# design.net
KiCad netlist of a schematic drawn in Altium Designer
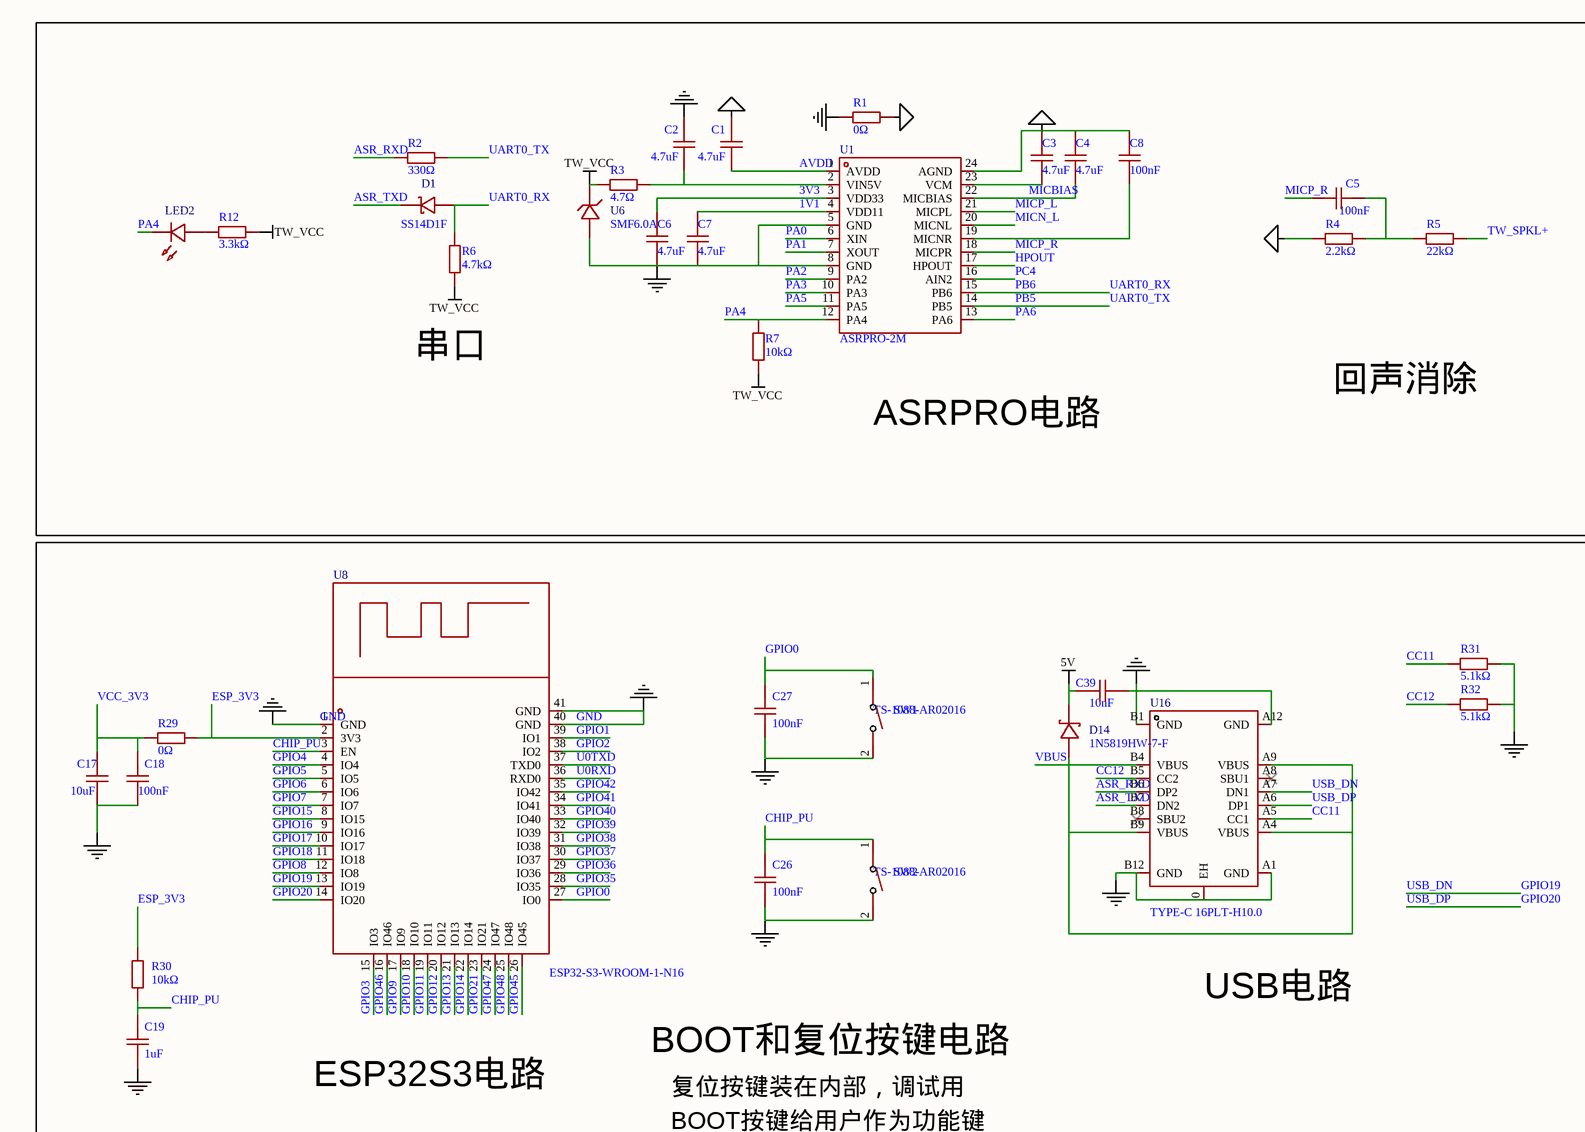
[diagram p0: 遥控器板子.schdoc, top left]
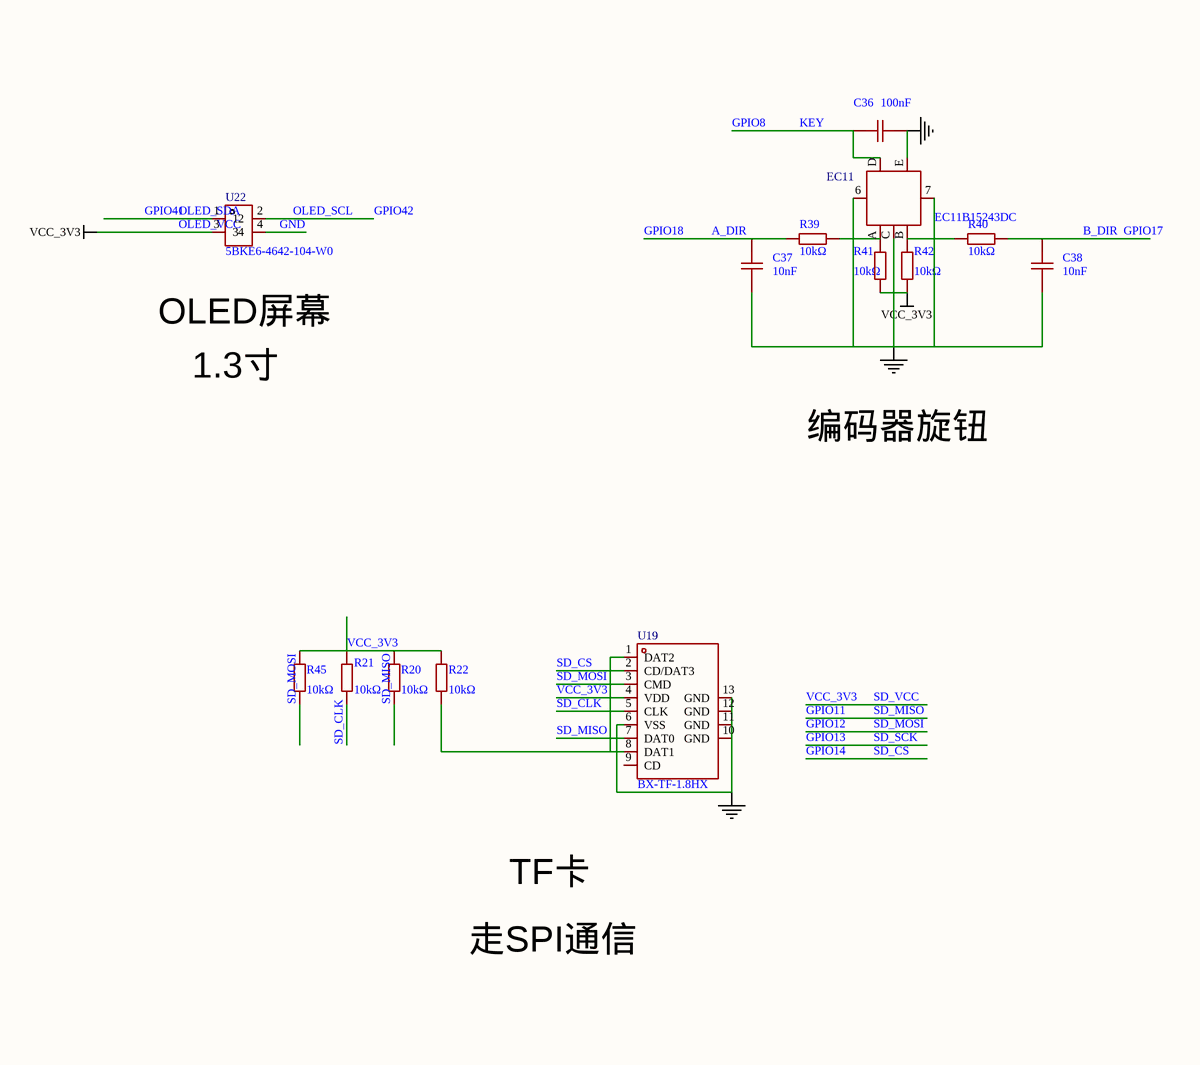
[diagram p1: 遥控器板子.schdoc, top right]
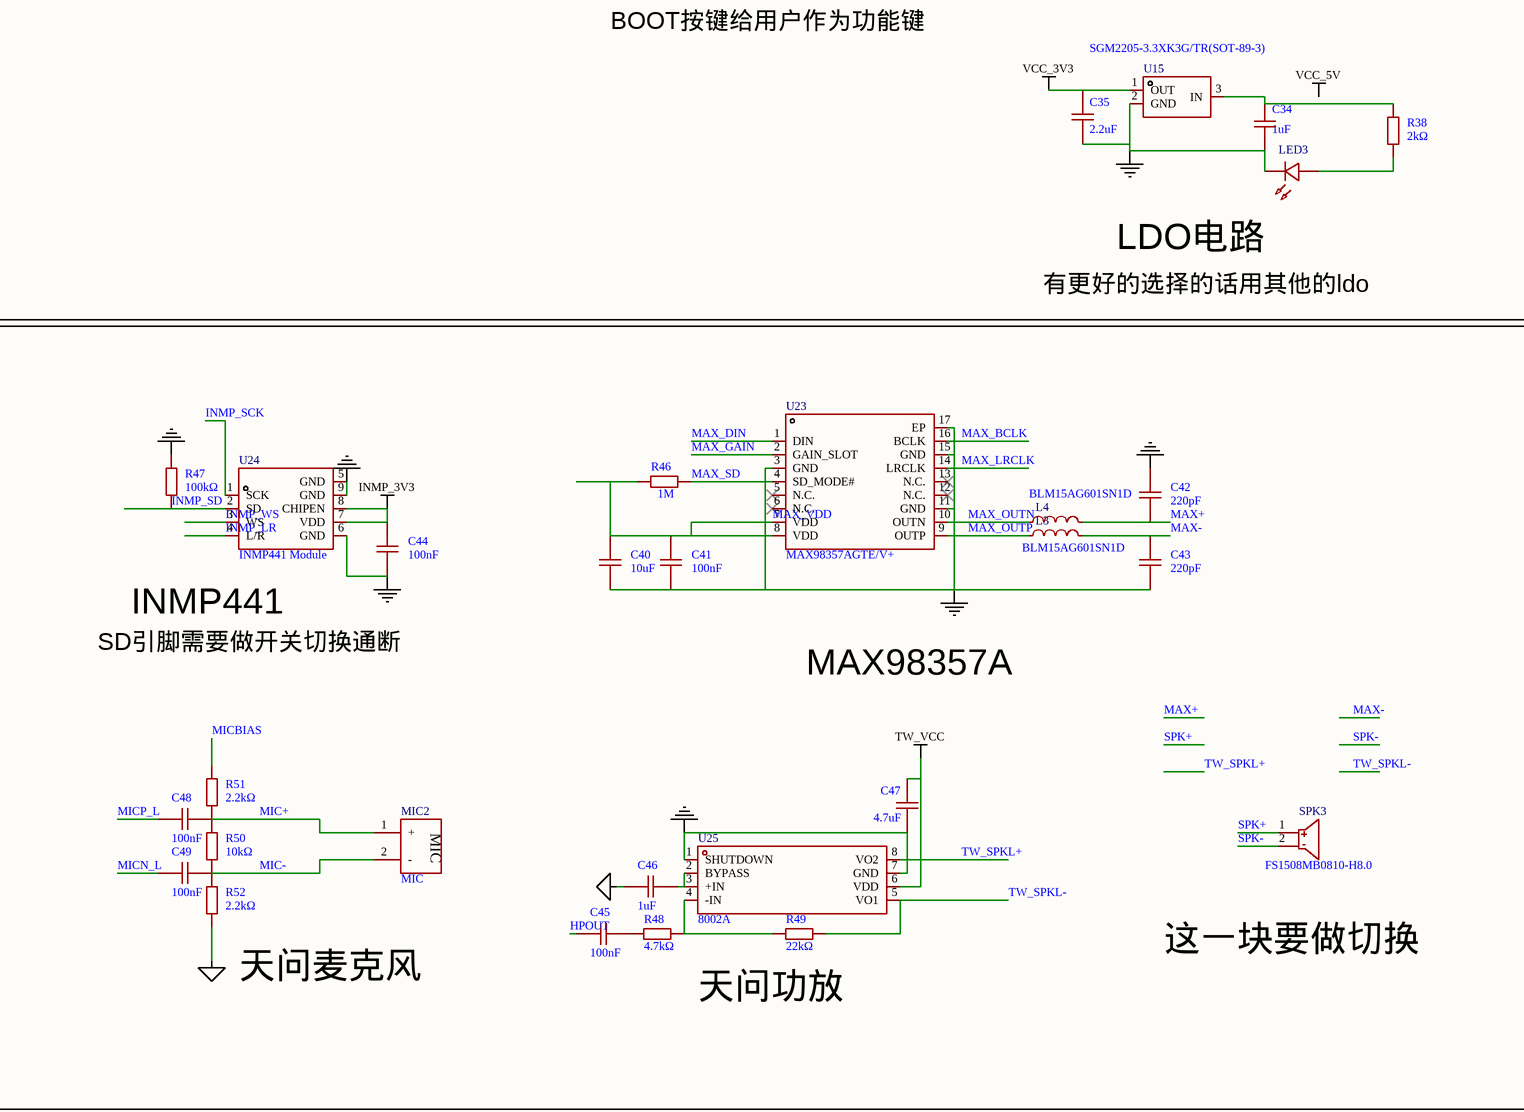
[diagram p2: 遥控器板子.schdoc, bottom left]
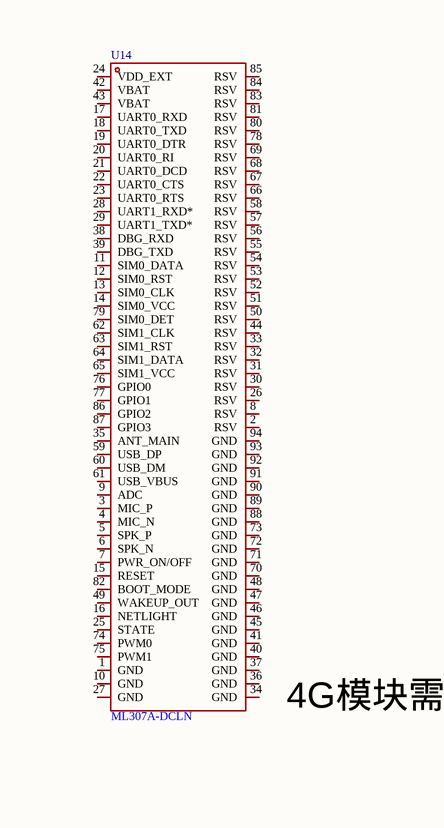
[diagram p3: 遥控器板子.schdoc, bottom right]

(export (version "E")
  (design (tool "Eeschema 10.0.6"))
  (components
    (comp (ref "C1")
      (value "4.7uF")
      (footprint "C0402")
      (fields
        (field (name "MANUFACTURER") "SAMSUNG(三星)")
        (field (name "MANUFACTURER PART") "CL05A475MP5NRNC")
        (field (name "TOLERANCE") "±20%")
      )
      (libsource (lib "altium-import") (part "root_1_CL05A475MP5NRNC_"))
    )
    (comp (ref "C2")
      (value "4.7uF")
      (footprint "C0402")
      (fields
        (field (name "MANUFACTURER") "SAMSUNG(三星)")
        (field (name "MANUFACTURER PART") "CL05A475MP5NRNC")
        (field (name "TOLERANCE") "±20%")
      )
      (libsource (lib "altium-import") (part "root_1_CL05A475MP5NRNC_"))
    )
    (comp (ref "C3")
      (value "4.7uF")
      (footprint "C0402")
      (fields
        (field (name "MANUFACTURER") "SAMSUNG(三星)")
        (field (name "MANUFACTURER PART") "CL05A475MP5NRNC")
        (field (name "TOLERANCE") "±20%")
      )
      (libsource (lib "altium-import") (part "root_1_CL05A475MP5NRNC_"))
    )
    (comp (ref "C4")
      (value "4.7uF")
      (footprint "C0402")
      (fields
        (field (name "MANUFACTURER") "SAMSUNG(三星)")
        (field (name "MANUFACTURER PART") "CL05A475MP5NRNC")
        (field (name "TOLERANCE") "±20%")
      )
      (libsource (lib "altium-import") (part "root_1_CL05A475MP5NRNC_"))
    )
    (comp (ref "C5")
      (value "100nF")
      (footprint "C0402")
      (fields
        (field (name "MANUFACTURER") "SAMSUNG(三星)")
        (field (name "MANUFACTURER PART") "CL05B104KO5NNNC")
        (field (name "TOLERANCE") "±10%")
      )
      (libsource (lib "altium-import") (part "root_0_CL05B104KO5NNNC_"))
    )
    (comp (ref "C6")
      (value "4.7uF")
      (footprint "C0402")
      (fields
        (field (name "MANUFACTURER") "SAMSUNG(三星)")
        (field (name "MANUFACTURER PART") "CL05A475MP5NRNC")
        (field (name "TOLERANCE") "±20%")
      )
      (libsource (lib "altium-import") (part "root_1_CL05A475MP5NRNC_"))
    )
    (comp (ref "C7")
      (value "4.7uF")
      (footprint "C0402")
      (fields
        (field (name "MANUFACTURER") "SAMSUNG(三星)")
        (field (name "MANUFACTURER PART") "CL05A475MP5NRNC")
        (field (name "TOLERANCE") "±20%")
      )
      (libsource (lib "altium-import") (part "root_1_CL05A475MP5NRNC_"))
    )
    (comp (ref "C8")
      (value "100nF")
      (footprint "C0402")
      (fields
        (field (name "MANUFACTURER") "SAMSUNG(三星)")
        (field (name "MANUFACTURER PART") "CL05B104KO5NNNC")
        (field (name "TOLERANCE") "±10%")
      )
      (libsource (lib "altium-import") (part "root_1_CL05B104KO5NNNC_"))
    )
    (comp (ref "C17")
      (value "10uF")
      (footprint "C0402")
      (fields
        (field (name "MANUFACTURER") "SAMSUNG(三星)")
        (field (name "MANUFACTURER PART") "CL05A106MQ5NUNC")
        (field (name "TOLERANCE") "±20%")
      )
      (libsource (lib "altium-import") (part "root_1_CL05A106MQ5NUNC_"))
    )
    (comp (ref "C18")
      (value "100nF")
      (footprint "C0402")
      (fields
        (field (name "MANUFACTURER") "SAMSUNG(三星)")
        (field (name "MANUFACTURER PART") "CL05B104KO5NNNC")
        (field (name "TOLERANCE") "±10%")
      )
      (libsource (lib "altium-import") (part "root_1_CL05B104KO5NNNC_"))
    )
    (comp (ref "C19")
      (value "1uF")
      (footprint "C0402")
      (fields
        (field (name "MANUFACTURER") "SAMSUNG(三星)")
        (field (name "MANUFACTURER PART") "CL05A105KP5NNNC")
        (field (name "TOLERANCE") "±10%")
      )
      (libsource (lib "altium-import") (part "root_1_CL05A105KP5NNNC_"))
    )
    (comp (ref "C26")
      (value "100nF")
      (footprint "C0402")
      (fields
        (field (name "MANUFACTURER") "SAMSUNG(三星)")
        (field (name "MANUFACTURER PART") "CL05B104KO5NNNC")
        (field (name "TOLERANCE") "±10%")
      )
      (libsource (lib "altium-import") (part "root_1_CL05B104KO5NNNC_"))
    )
    (comp (ref "C27")
      (value "100nF")
      (footprint "C0402")
      (fields
        (field (name "MANUFACTURER") "SAMSUNG(三星)")
        (field (name "MANUFACTURER PART") "CL05B104KO5NNNC")
        (field (name "TOLERANCE") "±10%")
      )
      (libsource (lib "altium-import") (part "root_1_CL05B104KO5NNNC_"))
    )
    (comp (ref "C34")
      (value "1uF")
      (footprint "C0402")
      (fields
        (field (name "MANUFACTURER") "SAMSUNG(三星)")
        (field (name "MANUFACTURER PART") "CL05A105KP5NNNC")
        (field (name "TOLERANCE") "±10%")
      )
      (libsource (lib "altium-import") (part "root_1_CL05A105KP5NNNC_"))
    )
    (comp (ref "C35")
      (value "2.2uF")
      (footprint "C0402")
      (fields
        (field (name "MANUFACTURER") "SAMSUNG(三星)")
        (field (name "MANUFACTURER PART") "CL05A225MQ5NSNC")
        (field (name "TOLERANCE") "±20%")
      )
      (libsource (lib "altium-import") (part "root_3_CL05A225MQ5NSNC_"))
    )
    (comp (ref "C36")
      (value "100nF")
      (footprint "C0402")
      (fields
        (field (name "MANUFACTURER") "SAMSUNG(三星)")
        (field (name "MANUFACTURER PART") "CL05B104KO5NNNC")
        (field (name "TOLERANCE") "±10%")
      )
      (libsource (lib "altium-import") (part "root_2_CL05B104KO5NNNC_"))
    )
    (comp (ref "C37")
      (value "10nF")
      (footprint "C0402")
      (fields
        (field (name "MANUFACTURER") "SAMSUNG(三星)")
        (field (name "MANUFACTURER PART") "CL05B103KB5NNNC")
        (field (name "TOLERANCE") "±10%")
      )
      (libsource (lib "altium-import") (part "root_1_CL05B103KB5NNNC_"))
    )
    (comp (ref "C38")
      (value "10nF")
      (footprint "C0402")
      (fields
        (field (name "MANUFACTURER") "SAMSUNG(三星)")
        (field (name "MANUFACTURER PART") "CL05B103KB5NNNC")
        (field (name "TOLERANCE") "±10%")
      )
      (libsource (lib "altium-import") (part "root_1_CL05B103KB5NNNC_"))
    )
    (comp (ref "C39")
      (value "10nF")
      (footprint "C0402")
      (fields
        (field (name "MANUFACTURER") "SAMSUNG(三星)")
        (field (name "MANUFACTURER PART") "CL05B103KB5NNNC")
        (field (name "TOLERANCE") "±10%")
      )
      (libsource (lib "altium-import") (part "root_0_CL05B103KB5NNNC_"))
    )
    (comp (ref "C40")
      (value "10uF")
      (footprint "C0402")
      (fields
        (field (name "MANUFACTURER") "SAMSUNG(三星)")
        (field (name "MANUFACTURER PART") "CL05A106MQ5NUNC")
        (field (name "TOLERANCE") "±20%")
      )
      (libsource (lib "altium-import") (part "root_1_CL05A106MQ5NUNC_"))
    )
    (comp (ref "C41")
      (value "100nF")
      (footprint "C0402")
      (fields
        (field (name "MANUFACTURER") "SAMSUNG(三星)")
        (field (name "MANUFACTURER PART") "CL05B104KO5NNNC")
        (field (name "TOLERANCE") "±10%")
      )
      (libsource (lib "altium-import") (part "root_1_CL05B104KO5NNNC_"))
    )
    (comp (ref "C42")
      (value "220pF")
      (footprint "C0402")
      (libsource (lib "altium-import") (part "root_1_CAP_0402_"))
    )
    (comp (ref "C43")
      (value "220pF")
      (footprint "C0402")
      (libsource (lib "altium-import") (part "root_1_CAP_0402_"))
    )
    (comp (ref "C44")
      (value "100nF")
      (footprint "C0402")
      (fields
        (field (name "MANUFACTURER") "SAMSUNG(三星)")
        (field (name "MANUFACTURER PART") "CL05B104KO5NNNC")
        (field (name "TOLERANCE") "±10%")
      )
      (libsource (lib "altium-import") (part "root_1_CL05B104KO5NNNC_"))
    )
    (comp (ref "C45")
      (value "100nF")
      (footprint "C0402")
      (fields
        (field (name "MANUFACTURER") "SAMSUNG(三星)")
        (field (name "MANUFACTURER PART") "CL05B104KO5NNNC")
        (field (name "TOLERANCE") "±10%")
      )
      (libsource (lib "altium-import") (part "root_2_CL05B104KO5NNNC_"))
    )
    (comp (ref "C46")
      (value "1uF")
      (footprint "C0402")
      (fields
        (field (name "MANUFACTURER") "SAMSUNG(三星)")
        (field (name "MANUFACTURER PART") "CL05A105KP5NNNC")
        (field (name "TOLERANCE") "±10%")
      )
      (libsource (lib "altium-import") (part "root_2_CL05A105KP5NNNC_"))
    )
    (comp (ref "C47")
      (value "4.7uF")
      (footprint "C0402")
      (fields
        (field (name "MANUFACTURER") "SAMSUNG(三星)")
        (field (name "MANUFACTURER PART") "CL05A475MP5NRNC")
        (field (name "TOLERANCE") "±20%")
      )
      (libsource (lib "altium-import") (part "root_3_CL05A475MP5NRNC_"))
    )
    (comp (ref "C48")
      (value "100nF")
      (footprint "C0402")
      (fields
        (field (name "MANUFACTURER") "SAMSUNG(三星)")
        (field (name "MANUFACTURER PART") "CL05B104KO5NNNC")
        (field (name "TOLERANCE") "±10%")
      )
      (libsource (lib "altium-import") (part "root_2_CL05B104KO5NNNC_"))
    )
    (comp (ref "C49")
      (value "100nF")
      (footprint "C0402")
      (fields
        (field (name "MANUFACTURER") "SAMSUNG(三星)")
        (field (name "MANUFACTURER PART") "CL05B104KO5NNNC")
        (field (name "TOLERANCE") "±10%")
      )
      (libsource (lib "altium-import") (part "root_2_CL05B104KO5NNNC_"))
    )
    (comp (ref "D1")
      (value "SS14D1F")
      (footprint "SOD-123_L2.8-W1.8-LS3.7-RD")
      (fields (field (name "MANUFACTURER") "PN SILICON(智晶)"))
      (libsource (lib "altium-import") (part "root_0_SS14D1F_"))
    )
    (comp (ref "D14")
      (value "1N5819HW-7-F")
      (footprint "SOD-123_L2.7-W1.6-LS3.7-RD")
      (fields (field (name "MANUFACTURER") "DIODES(美台)"))
      (libsource (lib "altium-import") (part "root_3_1N5819HW-7-F_"))
    )
    (comp (ref "EC11")
      (value "EC11B15243DC")
      (footprint "SW-TH_EC11B15243DC")
      (fields (field (name "MANUFACTURER") "ALPSALPINE(阿尔卑斯阿尔派)"))
      (libsource (lib "altium-import") (part "root_0_EC11B15243DC_"))
    )
    (comp (ref "L3")
      (value "BLM15AG601SN1D")
      (footprint "L0402")
      (fields (field (name "MANUFACTURER") "muRata(村田)") (field (name "TOLERANCE") "±25%"))
      (libsource (lib "altium-import") (part "root_0_BLM15AG601SN1D_"))
    )
    (comp (ref "L4")
      (value "BLM15AG601SN1D")
      (footprint "L0402")
      (fields (field (name "MANUFACTURER") "muRata(村田)") (field (name "TOLERANCE") "±25%"))
      (libsource (lib "altium-import") (part "root_0_BLM15AG601SN1D_"))
    )
    (comp (ref "LED2")
      (value "~")
      (footprint "LED_0402")
      (libsource (lib "altium-import") (part "root_2_LED_0603-R_"))
    )
    (comp (ref "LED3")
      (value "~")
      (footprint "LED_0402")
      (libsource (lib "altium-import") (part "root_2_LED_0603-R_"))
    )
    (comp (ref "MIC2")
      (value "MIC")
      (footprint "MIC-TH_BD6.0-P2.00")
      (libsource (lib "altium-import") (part "root_3_MIC_"))
    )
    (comp (ref "R1")
      (value "0Ω")
      (footprint "R0402")
      (fields
        (field (name "MANUFACTURER") "UNI-ROYAL(厚声)")
        (field (name "MANUFACTURER PART") "0402WGF0000TCE")
        (field (name "TOLERANCE") "±1%")
      )
      (libsource (lib "altium-import") (part "root_0_0402WGF0000TCE_"))
    )
    (comp (ref "R2")
      (value "330Ω")
      (footprint "R0402")
      (fields
        (field (name "MANUFACTURER") "UNI-ROYAL(厚声)")
        (field (name "MANUFACTURER PART") "0402WGF3300TCE")
        (field (name "TOLERANCE") "±1%")
      )
      (libsource (lib "altium-import") (part "root_0_0402WGF3300TCE_"))
    )
    (comp (ref "R3")
      (value "4.7Ω")
      (footprint "R0402")
      (fields
        (field (name "MANUFACTURER") "FOJAN(富捷)")
        (field (name "MANUFACTURER PART") "FRC0402F4R70TS")
        (field (name "TOLERANCE") "±1%")
      )
      (libsource (lib "altium-import") (part "root_0_FRC0402F4R70TS_"))
    )
    (comp (ref "R4")
      (value "2.2kΩ")
      (footprint "R0402")
      (fields
        (field (name "MANUFACTURER") "UNI-ROYAL(厚声)")
        (field (name "MANUFACTURER PART") "0402WGF2201TCE")
        (field (name "TOLERANCE") "±1%")
      )
      (libsource (lib "altium-import") (part "root_0_0402WGF2201TCE_"))
    )
    (comp (ref "R5")
      (value "22kΩ")
      (footprint "R0402")
      (fields
        (field (name "MANUFACTURER") "UNI-ROYAL(厚声)")
        (field (name "MANUFACTURER PART") "0402WGF2202TCE")
        (field (name "TOLERANCE") "±1%")
      )
      (libsource (lib "altium-import") (part "root_0_0402WGF2202TCE_"))
    )
    (comp (ref "R6")
      (value "4.7kΩ")
      (footprint "R0402")
      (fields
        (field (name "MANUFACTURER") "UNI-ROYAL(厚声)")
        (field (name "MANUFACTURER PART") "0402WGF4701TCE")
        (field (name "TOLERANCE") "±1%")
      )
      (libsource (lib "altium-import") (part "root_1_0402WGF4701TCE_"))
    )
    (comp (ref "R7")
      (value "10kΩ")
      (footprint "R0402")
      (fields
        (field (name "MANUFACTURER") "UNI-ROYAL(厚声)")
        (field (name "MANUFACTURER PART") "0402WGF1002TCE")
        (field (name "TOLERANCE") "±1%")
      )
      (libsource (lib "altium-import") (part "root_1_0402WGF1002TCE_"))
    )
    (comp (ref "R12")
      (value "3.3kΩ")
      (footprint "R0402")
      (fields
        (field (name "MANUFACTURER") "UNI-ROYAL(厚声)")
        (field (name "MANUFACTURER PART") "0402WGF3301TCE")
        (field (name "TOLERANCE") "±1%")
      )
      (libsource (lib "altium-import") (part "root_2_0402WGF3301TCE_"))
    )
    (comp (ref "R20")
      (value "10kΩ")
      (footprint "R0402")
      (fields
        (field (name "MANUFACTURER") "UNI-ROYAL(厚声)")
        (field (name "MANUFACTURER PART") "0402WGF1002TCE")
        (field (name "TOLERANCE") "±1%")
      )
      (libsource (lib "altium-import") (part "root_3_0402WGF1002TCE_"))
    )
    (comp (ref "R21")
      (value "10kΩ")
      (footprint "R0402")
      (fields
        (field (name "MANUFACTURER") "UNI-ROYAL(厚声)")
        (field (name "MANUFACTURER PART") "0402WGF1002TCE")
        (field (name "TOLERANCE") "±1%")
      )
      (libsource (lib "altium-import") (part "root_3_0402WGF1002TCE_"))
    )
    (comp (ref "R22")
      (value "10kΩ")
      (footprint "R0402")
      (fields
        (field (name "MANUFACTURER") "UNI-ROYAL(厚声)")
        (field (name "MANUFACTURER PART") "0402WGF1002TCE")
        (field (name "TOLERANCE") "±1%")
      )
      (libsource (lib "altium-import") (part "root_3_0402WGF1002TCE_"))
    )
    (comp (ref "R29")
      (value "0Ω")
      (footprint "R0402")
      (fields
        (field (name "MANUFACTURER") "UNI-ROYAL(厚声)")
        (field (name "MANUFACTURER PART") "0402WGF0000TCE")
        (field (name "TOLERANCE") "±1%")
      )
      (libsource (lib "altium-import") (part "root_0_0402WGF0000TCE_"))
    )
    (comp (ref "R30")
      (value "10kΩ")
      (footprint "R0402")
      (fields
        (field (name "MANUFACTURER") "UNI-ROYAL(厚声)")
        (field (name "MANUFACTURER PART") "0402WGF1002TCE")
        (field (name "TOLERANCE") "±1%")
      )
      (libsource (lib "altium-import") (part "root_1_0402WGF1002TCE_"))
    )
    (comp (ref "R31")
      (value "5.1kΩ")
      (footprint "R0402")
      (fields
        (field (name "MANUFACTURER") "UNI-ROYAL(厚声)")
        (field (name "MANUFACTURER PART") "0402WGF5101TCE")
        (field (name "TOLERANCE") "±1%")
      )
      (libsource (lib "altium-import") (part "root_0_0402WGF5101TCE_"))
    )
    (comp (ref "R32")
      (value "5.1kΩ")
      (footprint "R0402")
      (fields
        (field (name "MANUFACTURER") "UNI-ROYAL(厚声)")
        (field (name "MANUFACTURER PART") "0402WGF5101TCE")
        (field (name "TOLERANCE") "±1%")
      )
      (libsource (lib "altium-import") (part "root_0_0402WGF5101TCE_"))
    )
    (comp (ref "R38")
      (value "2kΩ")
      (footprint "R0402")
      (fields
        (field (name "MANUFACTURER") "UNI-ROYAL(厚声)")
        (field (name "MANUFACTURER PART") "0402WGF2001TCE")
        (field (name "TOLERANCE") "±1%")
      )
      (libsource (lib "altium-import") (part "root_1_0402WGF2001TCE_"))
    )
    (comp (ref "R39")
      (value "10kΩ")
      (footprint "R0402")
      (fields
        (field (name "MANUFACTURER") "UNI-ROYAL(厚声)")
        (field (name "MANUFACTURER PART") "0402WGF1002TCE")
        (field (name "TOLERANCE") "±1%")
      )
      (libsource (lib "altium-import") (part "root_2_0402WGF1002TCE_"))
    )
    (comp (ref "R40")
      (value "10kΩ")
      (footprint "R0402")
      (fields
        (field (name "MANUFACTURER") "UNI-ROYAL(厚声)")
        (field (name "MANUFACTURER PART") "0402WGF1002TCE")
        (field (name "TOLERANCE") "±1%")
      )
      (libsource (lib "altium-import") (part "root_2_0402WGF1002TCE_"))
    )
    (comp (ref "R41")
      (value "10kΩ")
      (footprint "R0402")
      (fields
        (field (name "MANUFACTURER") "UNI-ROYAL(厚声)")
        (field (name "MANUFACTURER PART") "0402WGF1002TCE")
        (field (name "TOLERANCE") "±1%")
      )
      (libsource (lib "altium-import") (part "root_1_0402WGF1002TCE_"))
    )
    (comp (ref "R42")
      (value "10kΩ")
      (footprint "R0402")
      (fields
        (field (name "MANUFACTURER") "UNI-ROYAL(厚声)")
        (field (name "MANUFACTURER PART") "0402WGF1002TCE")
        (field (name "TOLERANCE") "±1%")
      )
      (libsource (lib "altium-import") (part "root_3_0402WGF1002TCE_"))
    )
    (comp (ref "R45")
      (value "10kΩ")
      (footprint "R0402")
      (fields
        (field (name "MANUFACTURER") "UNI-ROYAL(厚声)")
        (field (name "MANUFACTURER PART") "0402WGF1002TCE")
        (field (name "TOLERANCE") "±1%")
      )
      (libsource (lib "altium-import") (part "root_3_0402WGF1002TCE_"))
    )
    (comp (ref "R46")
      (value "1M")
      (footprint "R0402")
      (libsource (lib "altium-import") (part "root_2_Res_0402_"))
    )
    (comp (ref "R47")
      (value "100kΩ")
      (footprint "R0402")
      (fields
        (field (name "MANUFACTURER") "UNI-ROYAL(厚声)")
        (field (name "MANUFACTURER PART") "0402WGF1003TCE")
        (field (name "TOLERANCE") "±1%")
      )
      (libsource (lib "altium-import") (part "root_1_0402WGF1003TCE_"))
    )
    (comp (ref "R48")
      (value "4.7kΩ")
      (footprint "R0402")
      (fields
        (field (name "MANUFACTURER") "UNI-ROYAL(厚声)")
        (field (name "MANUFACTURER PART") "0402WGF4701TCE")
        (field (name "TOLERANCE") "±1%")
      )
      (libsource (lib "altium-import") (part "root_0_0402WGF4701TCE_"))
    )
    (comp (ref "R49")
      (value "22kΩ")
      (footprint "R0402")
      (fields
        (field (name "MANUFACTURER") "UNI-ROYAL(厚声)")
        (field (name "MANUFACTURER PART") "0402WGF2202TCE")
        (field (name "TOLERANCE") "±1%")
      )
      (libsource (lib "altium-import") (part "root_2_0402WGF2202TCE_"))
    )
    (comp (ref "R50")
      (value "10kΩ")
      (footprint "R0402")
      (fields
        (field (name "MANUFACTURER") "UNI-ROYAL(厚声)")
        (field (name "MANUFACTURER PART") "0402WGF1002TCE")
        (field (name "TOLERANCE") "±1%")
      )
      (libsource (lib "altium-import") (part "root_1_0402WGF1002TCE_"))
    )
    (comp (ref "R51")
      (value "2.2kΩ")
      (footprint "R0402")
      (fields
        (field (name "MANUFACTURER") "UNI-ROYAL(厚声)")
        (field (name "MANUFACTURER PART") "0402WGF2201TCE")
        (field (name "TOLERANCE") "±1%")
      )
      (libsource (lib "altium-import") (part "root_1_0402WGF2201TCE_"))
    )
    (comp (ref "R52")
      (value "2.2kΩ")
      (footprint "R0402")
      (fields
        (field (name "MANUFACTURER") "UNI-ROYAL(厚声)")
        (field (name "MANUFACTURER PART") "0402WGF2201TCE")
        (field (name "TOLERANCE") "±1%")
      )
      (libsource (lib "altium-import") (part "root_3_0402WGF2201TCE_"))
    )
    (comp (ref "SPK3")
      (value "FS1508MB0810-H8.0")
      (footprint "BEEP-TH_BD15.0-P10.20-D1.2")
      (fields (field (name "MANUFACTURER") "FUET(福声科技)"))
      (libsource (lib "altium-import") (part "root_0_FS1508MB0810-H8.0_"))
    )
    (comp (ref "SW1")
      (value "TS-1088-AR02016")
      (footprint "SW-SMD_L3.9-W3.0-P4.45")
      (fields (field (name "MANUFACTURER") "XUNPU(讯普)"))
      (libsource (lib "altium-import") (part "root_3_TS-1088-AR02016_"))
    )
    (comp (ref "SW2")
      (value "TS-1088-AR02016")
      (footprint "SW-SMD_L3.9-W3.0-P4.45")
      (fields (field (name "MANUFACTURER") "XUNPU(讯普)"))
      (libsource (lib "altium-import") (part "root_3_TS-1088-AR02016_"))
    )
    (comp (ref "U1")
      (value "ASRPRO-2M")
      (footprint "SSOP-24_L8.7-W3.9-P0.64-LS6.0-BL-1")
      (libsource (lib "altium-import") (part "root_0_ASRPRO-2M_"))
    )
    (comp (ref "U6")
      (value "SMF6.0A")
      (footprint "SOD-123FL_L2.8-W1.8-LS3.8-RD")
      (fields (field (name "MANUFACTURER") "GOODWORK(固得沃克)"))
      (libsource (lib "altium-import") (part "root_3_SMF6.0A_"))
    )
    (comp (ref "U8")
      (value "ESP32-S3-WROOM-1-N16")
      (footprint "WIRELM-SMD_ESP32-S3-WROOM-1")
      (fields (field (name "MANUFACTURER") "ESPRESSIF(乐鑫)"))
      (libsource (lib "altium-import") (part "root_0_ESP32-S3-WROOM-1-N16_"))
    )
    (comp (ref "U14")
      (value "ML307A-DCLN")
      (footprint "LGA-94_L17.7-W15.8_N706-CA-01-S1")
      (libsource (lib "altium-import") (part "root_0_ML307A-DCLN_C9900089086_"))
    )
    (comp (ref "U15")
      (value "SGM2205-3.3XK3G/TR(SOT-89-3)")
      (footprint "SOT-89-3_L4.3-W2.3-P1.50-LS4.3-BR")
      (libsource (lib "altium-import") (part "root_0_SGM2205-3.3XK3G/TR(SOT-89-3)_"))
    )
    (comp (ref "U16")
      (value "TYPE-C 16PLT-H10.0")
      (footprint "TYPE-C-SMD_USB4120-03-C")
      (fields (field (name "MANUFACTURER") "SHOU HAN(首韩)"))
      (libsource (lib "altium-import") (part "root_0_TYPE-C 16PLT-H10.0_"))
    )
    (comp (ref "U19")
      (value "BX-TF-1.8HX")
      (footprint "TF-SMD_BX-TF-1.8HJ")
      (fields (field (name "MANUFACTURER") "Bossie(博锡)"))
      (libsource (lib "altium-import") (part "root_0_BX-TF-1.8HX_"))
    )
    (comp (ref "U22")
      (value "5BKE6-4642-104-W0")
      (footprint "CONN-SMD_4P-P1.99_5BKE6-4642-104-W0")
      (fields (field (name "MANUFACTURER") "SAMZO(三佐)"))
      (libsource (lib "altium-import") (part "root_0_5BKE6-4642-104-W0_"))
    )
    (comp (ref "U23")
      (value "MAX98357AGTE/V+")
      (footprint "TQFN-16_L3.0-W3.0-P0.50-BL-EP1.1")
      (fields (field (name "MANUFACTURER") "ADI(亚德诺)/MAXIM(美信)"))
      (libsource (lib "altium-import") (part "root_0_MAX98357AGTE/V+_"))
    )
    (comp (ref "U24")
      (value "INMP441 Module")
      (footprint "MID-SMD_L4.7-W3.8_INMP441ACEZ")
      (libsource (lib "altium-import") (part "root_0_INMP441 Module_"))
    )
    (comp (ref "U25")
      (value "8002A")
      (footprint "SOP-8_L4.9-W3.9-P1.27-LS6.0-BL")
      (fields (field (name "MANUFACTURER") "IDCHIP(英锐芯)"))
      (libsource (lib "altium-import") (part "root_0_8002A_"))
    )
  )
  (nets
    (net (code "1") (name "/1V1") (class "Default")
      (node (ref "C7") (pin "2") (pinfunction "2_2") (pintype "passive"))
      (node (ref "U1") (pin "4") (pinfunction "VDD11_4") (pintype "passive"))
    )
    (net (code "2") (name "/3V3") (class "Default")
      (node (ref "C6") (pin "2") (pinfunction "2_2") (pintype "passive"))
      (node (ref "U1") (pin "3") (pinfunction "VDD33_3") (pintype "passive"))
    )
    (net (code "3") (name "/ASR_RXD") (class "Default")
      (node (ref "R2") (pin "1") (pinfunction "1_1") (pintype "passive"))
      (node (ref "U16") (pin "B6") (pinfunction "DP2_B6") (pintype "passive"))
    )
    (net (code "4") (name "/ASR_TXD") (class "Default")
      (node (ref "D1") (pin "1") (pinfunction "1_1") (pintype "passive"))
      (node (ref "U16") (pin "B7") (pinfunction "DN2_B7") (pintype "passive"))
    )
    (net (code "5") (name "/AVDD") (class "Default")
      (node (ref "C1") (pin "1") (pinfunction "1_1") (pintype "passive"))
      (node (ref "U1") (pin "1") (pinfunction "AVDD_1") (pintype "passive"))
    )
    (net (code "6") (name "/A_DIR") (class "Default")
      (node (ref "C37") (pin "2") (pinfunction "2_2") (pintype "passive"))
      (node (ref "R39") (pin "2") (pinfunction "2_2") (pintype "passive"))
      (node (ref "U8") (pin "11") (pinfunction "IO18_11") (pintype "passive"))
    )
    (net (code "7") (name "/B_DIR") (class "Default")
      (node (ref "C38") (pin "2") (pinfunction "2_2") (pintype "passive"))
      (node (ref "R40") (pin "1") (pinfunction "1_1") (pintype "passive"))
      (node (ref "U8") (pin "10") (pinfunction "IO17_10") (pintype "passive"))
    )
    (net (code "8") (name "/CC11") (class "Default")
      (node (ref "R31") (pin "1") (pinfunction "1_1") (pintype "passive"))
      (node (ref "U16") (pin "A5") (pinfunction "CC1_A5") (pintype "passive"))
    )
    (net (code "9") (name "/CC12") (class "Default")
      (node (ref "R32") (pin "1") (pinfunction "1_1") (pintype "passive"))
      (node (ref "U16") (pin "B5") (pinfunction "CC2_B5") (pintype "passive"))
    )
    (net (code "10") (name "/CHIP_PU") (class "Default")
      (node (ref "C19") (pin "2") (pinfunction "2_2") (pintype "passive"))
      (node (ref "C26") (pin "2") (pinfunction "2_2") (pintype "passive"))
      (node (ref "R30") (pin "1") (pinfunction "1_1") (pintype "passive"))
      (node (ref "SW2") (pin "1") (pinfunction "1_1") (pintype "passive"))
      (node (ref "U8") (pin "3") (pinfunction "EN_3") (pintype "passive"))
    )
    (net (code "11") (name "/ESP_3V3") (class "Default")
      (node (ref "R29") (pin "2") (pinfunction "2_2") (pintype "passive"))
      (node (ref "R30") (pin "2") (pinfunction "2_2") (pintype "passive"))
      (node (ref "U8") (pin "2") (pinfunction "3V3_2") (pintype "passive"))
    )
    (net (code "12") (name "/GPIO0") (class "Default")
      (node (ref "C27") (pin "2") (pinfunction "2_2") (pintype "passive"))
      (node (ref "SW1") (pin "1") (pinfunction "1_1") (pintype "passive"))
      (node (ref "U8") (pin "27") (pinfunction "IO0_27") (pintype "passive"))
    )
    (net (code "13") (name "/GPIO1") (class "Default")
      (node (ref "U8") (pin "39") (pinfunction "IO1_39") (pintype "passive"))
    )
    (net (code "14") (name "/GPIO2") (class "Default")
      (node (ref "U8") (pin "38") (pinfunction "IO2_38") (pintype "passive"))
    )
    (net (code "15") (name "/GPIO3") (class "Default")
      (node (ref "U8") (pin "15") (pinfunction "IO3_15") (pintype "passive"))
    )
    (net (code "16") (name "/GPIO4") (class "Default")
      (node (ref "U8") (pin "4") (pinfunction "IO4_4") (pintype "passive"))
    )
    (net (code "17") (name "/GPIO5") (class "Default")
      (node (ref "U8") (pin "5") (pinfunction "IO5_5") (pintype "passive"))
    )
    (net (code "18") (name "/GPIO6") (class "Default")
      (node (ref "U8") (pin "6") (pinfunction "IO6_6") (pintype "passive"))
    )
    (net (code "19") (name "/GPIO7") (class "Default")
      (node (ref "U8") (pin "7") (pinfunction "IO7_7") (pintype "passive"))
    )
    (net (code "20") (name "/GPIO8") (class "Default")
      (node (ref "C36") (pin "2") (pinfunction "2_2") (pintype "passive"))
      (node (ref "EC11") (pin "D") (pinfunction "D_D") (pintype "passive"))
      (node (ref "U8") (pin "12") (pinfunction "IO8_12") (pintype "passive"))
    )
    (net (code "21") (name "/GPIO9") (class "Default")
      (node (ref "U8") (pin "17") (pinfunction "IO9_17") (pintype "passive"))
    )
    (net (code "22") (name "/GPIO10") (class "Default")
      (node (ref "U8") (pin "18") (pinfunction "IO10_18") (pintype "passive"))
    )
    (net (code "23") (name "/GPIO11") (class "Default")
      (node (ref "R20") (pin "2") (pinfunction "2_2") (pintype "passive"))
      (node (ref "U19") (pin "7") (pinfunction "DAT0_7") (pintype "passive"))
      (node (ref "U8") (pin "19") (pinfunction "IO11_19") (pintype "passive"))
    )
    (net (code "24") (name "/GPIO12") (class "Default")
      (node (ref "R45") (pin "2") (pinfunction "2_2") (pintype "passive"))
      (node (ref "U19") (pin "3") (pinfunction "CMD_3") (pintype "passive"))
      (node (ref "U8") (pin "20") (pinfunction "IO12_20") (pintype "passive"))
    )
    (net (code "25") (name "/GPIO13") (class "Default")
      (node (ref "U8") (pin "21") (pinfunction "IO13_21") (pintype "passive"))
    )
    (net (code "26") (name "/GPIO14") (class "Default")
      (node (ref "U19") (pin "2") (pinfunction "CD/DAT3_2") (pintype "passive"))
      (node (ref "U8") (pin "22") (pinfunction "IO14_22") (pintype "passive"))
    )
    (net (code "27") (name "/GPIO15") (class "Default")
      (node (ref "U8") (pin "8") (pinfunction "IO15_8") (pintype "passive"))
    )
    (net (code "28") (name "/GPIO16") (class "Default")
      (node (ref "U8") (pin "9") (pinfunction "IO16_9") (pintype "passive"))
    )
    (net (code "29") (name "/GPIO19") (class "Default")
      (node (ref "U16") (pin "A7") (pinfunction "DN1_A7") (pintype "passive"))
      (node (ref "U8") (pin "13") (pinfunction "IO19_13") (pintype "passive"))
    )
    (net (code "30") (name "/GPIO20") (class "Default")
      (node (ref "U16") (pin "A6") (pinfunction "DP1_A6") (pintype "passive"))
      (node (ref "U8") (pin "14") (pinfunction "IO20_14") (pintype "passive"))
    )
    (net (code "31") (name "/GPIO21") (class "Default")
      (node (ref "U8") (pin "23") (pinfunction "IO21_23") (pintype "passive"))
    )
    (net (code "32") (name "/GPIO35") (class "Default")
      (node (ref "U8") (pin "28") (pinfunction "IO35_28") (pintype "passive"))
    )
    (net (code "33") (name "/GPIO36") (class "Default")
      (node (ref "U8") (pin "29") (pinfunction "IO36_29") (pintype "passive"))
    )
    (net (code "34") (name "/GPIO37") (class "Default")
      (node (ref "U8") (pin "30") (pinfunction "IO37_30") (pintype "passive"))
    )
    (net (code "35") (name "/GPIO38") (class "Default")
      (node (ref "U8") (pin "31") (pinfunction "IO38_31") (pintype "passive"))
    )
    (net (code "36") (name "/GPIO39") (class "Default")
      (node (ref "U8") (pin "32") (pinfunction "IO39_32") (pintype "passive"))
    )
    (net (code "37") (name "/GPIO40") (class "Default")
      (node (ref "U8") (pin "33") (pinfunction "IO40_33") (pintype "passive"))
    )
    (net (code "38") (name "/GPIO41") (class "Default")
      (node (ref "U22") (pin "1") (pinfunction "1_1") (pintype "passive"))
      (node (ref "U8") (pin "34") (pinfunction "IO41_34") (pintype "passive"))
    )
    (net (code "39") (name "/GPIO42") (class "Default")
      (node (ref "U22") (pin "2") (pinfunction "2_2") (pintype "passive"))
      (node (ref "U8") (pin "35") (pinfunction "IO42_35") (pintype "passive"))
    )
    (net (code "40") (name "/GPIO45") (class "Default")
      (node (ref "U8") (pin "26") (pinfunction "IO45_26") (pintype "passive"))
    )
    (net (code "41") (name "/GPIO46") (class "Default")
      (node (ref "U8") (pin "16") (pinfunction "IO46_16") (pintype "passive"))
    )
    (net (code "42") (name "/GPIO47") (class "Default")
      (node (ref "U8") (pin "24") (pinfunction "IO47_24") (pintype "passive"))
    )
    (net (code "43") (name "/GPIO48") (class "Default")
      (node (ref "U8") (pin "25") (pinfunction "IO48_25") (pintype "passive"))
    )
    (net (code "44") (name "/HPOUT") (class "Default")
      (node (ref "C45") (pin "2") (pinfunction "2_2") (pintype "passive"))
      (node (ref "U1") (pin "17") (pinfunction "HPOUT_17") (pintype "passive"))
    )
    (net (code "45") (name "/INMP_LR") (class "Default")
      (node (ref "U24") (pin "4") (pinfunction "L/R_4") (pintype "passive"))
    )
    (net (code "46") (name "/INMP_SCK") (class "Default")
      (node (ref "U24") (pin "1") (pinfunction "SCK_1") (pintype "passive"))
    )
    (net (code "47") (name "/INMP_SD") (class "Default")
      (node (ref "R47") (pin "1") (pinfunction "1_1") (pintype "passive"))
      (node (ref "U24") (pin "2") (pinfunction "SD_2") (pintype "passive"))
    )
    (net (code "48") (name "/INMP_WS") (class "Default")
      (node (ref "U24") (pin "3") (pinfunction "WS_3") (pintype "passive"))
    )
    (net (code "49") (name "/MAX+") (class "Default")
      (node (ref "C42") (pin "1") (pinfunction "1_1") (pintype "passive"))
      (node (ref "L4") (pin "2") (pinfunction "2_2") (pintype "passive"))
    )
    (net (code "50") (name "/MAX-") (class "Default")
      (node (ref "C43") (pin "2") (pinfunction "2_2") (pintype "passive"))
      (node (ref "L3") (pin "2") (pinfunction "2_2") (pintype "passive"))
    )
    (net (code "51") (name "/MAX_BCLK") (class "Default")
      (node (ref "U23") (pin "16") (pinfunction "BCLK_16") (pintype "passive"))
    )
    (net (code "52") (name "/MAX_DIN") (class "Default")
      (node (ref "U23") (pin "1") (pinfunction "DIN_1") (pintype "passive"))
    )
    (net (code "53") (name "/MAX_GAIN") (class "Default")
      (node (ref "U23") (pin "2") (pinfunction "GAIN_SLOT_2") (pintype "passive"))
    )
    (net (code "54") (name "/MAX_LRCLK") (class "Default")
      (node (ref "U23") (pin "14") (pinfunction "LRCLK_14") (pintype "passive"))
    )
    (net (code "55") (name "/MAX_OUTN") (class "Default")
      (node (ref "L4") (pin "1") (pinfunction "1_1") (pintype "passive"))
      (node (ref "U23") (pin "10") (pinfunction "OUTN_10") (pintype "passive"))
    )
    (net (code "56") (name "/MAX_OUTP") (class "Default")
      (node (ref "L3") (pin "1") (pinfunction "1_1") (pintype "passive"))
      (node (ref "U23") (pin "9") (pinfunction "OUTP_9") (pintype "passive"))
    )
    (net (code "57") (name "/MAX_SD") (class "Default")
      (node (ref "R46") (pin "1") (pinfunction "1_1") (pintype "passive"))
      (node (ref "U23") (pin "4") (pinfunction "SD_MODE#_4") (pintype "passive"))
    )
    (net (code "58") (name "/MAX_VDD") (class "Default")
      (node (ref "C40") (pin "2") (pinfunction "2_2") (pintype "passive"))
      (node (ref "C41") (pin "2") (pinfunction "2_2") (pintype "passive"))
      (node (ref "R46") (pin "2") (pinfunction "2_2") (pintype "passive"))
      (node (ref "U23") (pin "7") (pinfunction "VDD_7") (pintype "passive"))
      (node (ref "U23") (pin "8") (pinfunction "VDD_8") (pintype "passive"))
    )
    (net (code "59") (name "/MIC+") (class "Default")
      (node (ref "C48") (pin "1") (pinfunction "1_1") (pintype "passive"))
      (node (ref "MIC2") (pin "1") (pinfunction "+_1") (pintype "passive"))
      (node (ref "R50") (pin "2") (pinfunction "2_2") (pintype "passive"))
      (node (ref "R51") (pin "1") (pinfunction "1_1") (pintype "passive"))
    )
    (net (code "60") (name "/MIC-") (class "Default")
      (node (ref "C49") (pin "1") (pinfunction "1_1") (pintype "passive"))
      (node (ref "MIC2") (pin "2") (pinfunction "-_2") (pintype "passive"))
      (node (ref "R50") (pin "1") (pinfunction "1_1") (pintype "passive"))
      (node (ref "R52") (pin "1") (pinfunction "1_1") (pintype "passive"))
    )
    (net (code "61") (name "/MICBIAS") (class "Default")
      (node (ref "C4") (pin "1") (pinfunction "1_1") (pintype "passive"))
      (node (ref "R51") (pin "2") (pinfunction "2_2") (pintype "passive"))
      (node (ref "U1") (pin "22") (pinfunction "MICBIAS_22") (pintype "passive"))
    )
    (net (code "62") (name "/MICN_L") (class "Default")
      (node (ref "C49") (pin "2") (pinfunction "2_2") (pintype "passive"))
      (node (ref "U1") (pin "20") (pinfunction "MICNL_20") (pintype "passive"))
    )
    (net (code "63") (name "/MICP_L") (class "Default")
      (node (ref "C48") (pin "2") (pinfunction "2_2") (pintype "passive"))
      (node (ref "U1") (pin "21") (pinfunction "MICPL_21") (pintype "passive"))
    )
    (net (code "64") (name "/MICP_R") (class "Default")
      (node (ref "C5") (pin "1") (pinfunction "1_1") (pintype "passive"))
      (node (ref "U1") (pin "18") (pinfunction "MICPR_18") (pintype "passive"))
    )
    (net (code "65") (name "/PA0") (class "Default")
      (node (ref "U1") (pin "6") (pinfunction "XIN_6") (pintype "passive"))
    )
    (net (code "66") (name "/PA1") (class "Default")
      (node (ref "U1") (pin "7") (pinfunction "XOUT_7") (pintype "passive"))
    )
    (net (code "67") (name "/PA2") (class "Default")
      (node (ref "U1") (pin "9") (pinfunction "PA2_9") (pintype "passive"))
    )
    (net (code "68") (name "/PA3") (class "Default")
      (node (ref "U1") (pin "10") (pinfunction "PA3_10") (pintype "passive"))
    )
    (net (code "69") (name "/PA4") (class "Default")
      (node (ref "LED2") (pin "1") (pinfunction "C_1") (pintype "passive"))
      (node (ref "R7") (pin "2") (pinfunction "2_2") (pintype "passive"))
      (node (ref "U1") (pin "12") (pinfunction "PA4_12") (pintype "passive"))
    )
    (net (code "70") (name "/PA5") (class "Default")
      (node (ref "U1") (pin "11") (pinfunction "PA5_11") (pintype "passive"))
    )
    (net (code "71") (name "/PA6") (class "Default")
      (node (ref "U1") (pin "13") (pinfunction "PA6_13") (pintype "passive"))
    )
    (net (code "72") (name "/PB5") (class "Default")
      (node (ref "R2") (pin "2") (pinfunction "2_2") (pintype "passive"))
      (node (ref "U1") (pin "14") (pinfunction "PB5_14") (pintype "passive"))
    )
    (net (code "73") (name "/PB6") (class "Default")
      (node (ref "D1") (pin "2") (pinfunction "2_2") (pintype "passive"))
      (node (ref "R6") (pin "2") (pinfunction "2_2") (pintype "passive"))
      (node (ref "U1") (pin "15") (pinfunction "PB6_15") (pintype "passive"))
    )
    (net (code "74") (name "/PC4") (class "Default")
      (node (ref "U1") (pin "16") (pinfunction "AIN2_16") (pintype "passive"))
    )
    (net (code "75") (name "/SD_CLK") (class "Default")
      (node (ref "R21") (pin "2") (pinfunction "2_2") (pintype "passive"))
      (node (ref "U19") (pin "5") (pinfunction "CLK_5") (pintype "passive"))
    )
    (net (code "76") (name "/SPK+") (class "Default")
      (node (ref "SPK3") (pin "1") (pinfunction "1_1") (pintype "passive"))
    )
    (net (code "77") (name "/SPK-") (class "Default")
      (node (ref "SPK3") (pin "2") (pinfunction "2_2") (pintype "passive"))
    )
    (net (code "78") (name "/TW_SPKL+") (class "Default")
      (node (ref "R5") (pin "2") (pinfunction "2_2") (pintype "passive"))
      (node (ref "U25") (pin "8") (pinfunction "VO2_8") (pintype "passive"))
    )
    (net (code "79") (name "/TW_SPKL-") (class "Default")
      (node (ref "R49") (pin "1") (pinfunction "1_1") (pintype "passive"))
      (node (ref "U25") (pin "5") (pinfunction "VO1_5") (pintype "passive"))
    )
    (net (code "80") (name "/U0RXD") (class "Default")
      (node (ref "U8") (pin "36") (pinfunction "RXD0_36") (pintype "passive"))
    )
    (net (code "81") (name "/U0TXD") (class "Default")
      (node (ref "U8") (pin "37") (pinfunction "TXD0_37") (pintype "passive"))
    )
    (net (code "82") (name "/VBUS") (class "Default")
      (node (ref "D14") (pin "2") (pinfunction "A_2") (pintype "passive"))
      (node (ref "U16") (pin "A4") (pinfunction "VBUS_A4") (pintype "passive"))
      (node (ref "U16") (pin "A9") (pinfunction "VBUS_A9") (pintype "passive"))
      (node (ref "U16") (pin "B4") (pinfunction "VBUS_B4") (pintype "passive"))
      (node (ref "U16") (pin "B9") (pinfunction "VBUS_B9") (pintype "passive"))
    )
    (net (code "83") (name "5V") (class "Default")
      (node (ref "C39") (pin "1") (pinfunction "1_1") (pintype "passive"))
      (node (ref "D14") (pin "1") (pinfunction "K_1") (pintype "passive"))
    )
    (net (code "84") (name "AGND") (class "Default")
      (node (ref "C1") (pin "2") (pinfunction "2_2") (pintype "passive"))
      (node (ref "C3") (pin "2") (pinfunction "2_2") (pintype "passive"))
      (node (ref "C4") (pin "2") (pinfunction "2_2") (pintype "passive"))
      (node (ref "C46") (pin "2") (pinfunction "2_2") (pintype "passive"))
      (node (ref "C8") (pin "2") (pinfunction "2_2") (pintype "passive"))
      (node (ref "R1") (pin "2") (pinfunction "2_2") (pintype "passive"))
      (node (ref "R4") (pin "1") (pinfunction "1_1") (pintype "passive"))
      (node (ref "R52") (pin "2") (pinfunction "2_2") (pintype "passive"))
      (node (ref "U1") (pin "24") (pinfunction "AGND_24") (pintype "passive"))
    )
    (net (code "85") (name "GND") (class "Default")
      (node (ref "C17") (pin "1") (pinfunction "1_1") (pintype "passive"))
      (node (ref "C18") (pin "1") (pinfunction "1_1") (pintype "passive"))
      (node (ref "C19") (pin "1") (pinfunction "1_1") (pintype "passive"))
      (node (ref "C2") (pin "2") (pinfunction "2_2") (pintype "passive"))
      (node (ref "C26") (pin "1") (pinfunction "1_1") (pintype "passive"))
      (node (ref "C27") (pin "1") (pinfunction "1_1") (pintype "passive"))
      (node (ref "C34") (pin "1") (pinfunction "1_1") (pintype "passive"))
      (node (ref "C35") (pin "2") (pinfunction "2_2") (pintype "passive"))
      (node (ref "C36") (pin "1") (pinfunction "1_1") (pintype "passive"))
      (node (ref "C37") (pin "1") (pinfunction "1_1") (pintype "passive"))
      (node (ref "C38") (pin "1") (pinfunction "1_1") (pintype "passive"))
      (node (ref "C39") (pin "2") (pinfunction "2_2") (pintype "passive"))
      (node (ref "C40") (pin "1") (pinfunction "1_1") (pintype "passive"))
      (node (ref "C41") (pin "1") (pinfunction "1_1") (pintype "passive"))
      (node (ref "C42") (pin "2") (pinfunction "2_2") (pintype "passive"))
      (node (ref "C43") (pin "1") (pinfunction "1_1") (pintype "passive"))
      (node (ref "C44") (pin "1") (pinfunction "1_1") (pintype "passive"))
      (node (ref "C47") (pin "2") (pinfunction "2_2") (pintype "passive"))
      (node (ref "C6") (pin "1") (pinfunction "1_1") (pintype "passive"))
      (node (ref "C7") (pin "1") (pinfunction "1_1") (pintype "passive"))
      (node (ref "EC11") (pin "6") (pinfunction "EH_6") (pintype "passive"))
      (node (ref "EC11") (pin "7") (pinfunction "EH_7") (pintype "passive"))
      (node (ref "EC11") (pin "C") (pinfunction "C_C") (pintype "passive"))
      (node (ref "EC11") (pin "E") (pinfunction "E_E") (pintype "passive"))
      (node (ref "LED3") (pin "1") (pinfunction "C_1") (pintype "passive"))
      (node (ref "R1") (pin "1") (pinfunction "1_1") (pintype "passive"))
      (node (ref "R31") (pin "2") (pinfunction "2_2") (pintype "passive"))
      (node (ref "R32") (pin "2") (pinfunction "2_2") (pintype "passive"))
      (node (ref "R47") (pin "2") (pinfunction "2_2") (pintype "passive"))
      (node (ref "SW1") (pin "2") (pinfunction "2_2") (pintype "passive"))
      (node (ref "SW2") (pin "2") (pinfunction "2_2") (pintype "passive"))
      (node (ref "U1") (pin "5") (pinfunction "GND_5") (pintype "passive"))
      (node (ref "U1") (pin "8") (pinfunction "GND_8") (pintype "passive"))
      (node (ref "U15") (pin "2") (pinfunction "GND_2") (pintype "passive"))
      (node (ref "U16") (pin "0") (pinfunction "EH_0") (pintype "passive"))
      (node (ref "U16") (pin "A1") (pinfunction "GND_A1") (pintype "passive"))
      (node (ref "U16") (pin "A12") (pinfunction "GND_A12") (pintype "passive"))
      (node (ref "U16") (pin "B1") (pinfunction "GND_B1") (pintype "passive"))
      (node (ref "U16") (pin "B12") (pinfunction "GND_B12") (pintype "passive"))
      (node (ref "U19") (pin "10") (pinfunction "GND_10") (pintype "passive"))
      (node (ref "U19") (pin "11") (pinfunction "GND_11") (pintype "passive"))
      (node (ref "U19") (pin "12") (pinfunction "GND_12") (pintype "passive"))
      (node (ref "U19") (pin "13") (pinfunction "GND_13") (pintype "passive"))
      (node (ref "U19") (pin "6") (pinfunction "VSS_6") (pintype "passive"))
      (node (ref "U22") (pin "4") (pinfunction "4_4") (pintype "passive"))
      (node (ref "U23") (pin "11") (pinfunction "GND_11") (pintype "passive"))
      (node (ref "U23") (pin "15") (pinfunction "GND_15") (pintype "passive"))
      (node (ref "U23") (pin "17") (pinfunction "EP_17") (pintype "passive"))
      (node (ref "U23") (pin "3") (pinfunction "GND_3") (pintype "passive"))
      (node (ref "U24") (pin "5") (pinfunction "GND_5") (pintype "passive"))
      (node (ref "U24") (pin "6") (pinfunction "GND_6") (pintype "passive"))
      (node (ref "U24") (pin "9") (pinfunction "GND_9") (pintype "passive"))
      (node (ref "U25") (pin "1") (pinfunction "SHUTDOWN_1") (pintype "passive"))
      (node (ref "U25") (pin "7") (pinfunction "GND_7") (pintype "passive"))
      (node (ref "U6") (pin "2") (pinfunction "A_2") (pintype "passive"))
      (node (ref "U8") (pin "1") (pinfunction "GND_1") (pintype "passive"))
      (node (ref "U8") (pin "40") (pinfunction "GND_40") (pintype "passive"))
      (node (ref "U8") (pin "41") (pinfunction "GND_41") (pintype "passive"))
    )
    (net (code "86") (name "INMP_3V3") (class "Default")
      (node (ref "C44") (pin "2") (pinfunction "2_2") (pintype "passive"))
      (node (ref "U24") (pin "7") (pinfunction "VDD_7") (pintype "passive"))
      (node (ref "U24") (pin "8") (pinfunction "CHIPEN_8") (pintype "passive"))
    )
    (net (code "87") (name "Net-(C5-Pad2)") (class "Default")
      (node (ref "C5") (pin "2") (pinfunction "2_2") (pintype "passive"))
      (node (ref "R4") (pin "2") (pinfunction "2_2") (pintype "passive"))
      (node (ref "R5") (pin "1") (pinfunction "1_1") (pintype "passive"))
    )
    (net (code "88") (name "Net-(C45-Pad1)") (class "Default")
      (node (ref "C45") (pin "1") (pinfunction "1_1") (pintype "passive"))
      (node (ref "R48") (pin "1") (pinfunction "1_1") (pintype "passive"))
    )
    (net (code "89") (name "Net-(EC11-PadA)") (class "Default")
      (node (ref "EC11") (pin "A") (pinfunction "A_A") (pintype "passive"))
      (node (ref "R39") (pin "1") (pinfunction "1_1") (pintype "passive"))
      (node (ref "R41") (pin "2") (pinfunction "2_2") (pintype "passive"))
    )
    (net (code "90") (name "Net-(EC11-PadB)") (class "Default")
      (node (ref "EC11") (pin "B") (pinfunction "B_B") (pintype "passive"))
      (node (ref "R40") (pin "2") (pinfunction "2_2") (pintype "passive"))
      (node (ref "R42") (pin "1") (pinfunction "1_1") (pintype "passive"))
    )
    (net (code "91") (name "Net-(LED2-A)") (class "Default")
      (node (ref "LED2") (pin "2") (pinfunction "A_2") (pintype "passive"))
      (node (ref "R12") (pin "2") (pinfunction "2_2") (pintype "passive"))
    )
    (net (code "92") (name "Net-(LED3-A)") (class "Default")
      (node (ref "LED3") (pin "2") (pinfunction "A_2") (pintype "passive"))
      (node (ref "R38") (pin "1") (pinfunction "1_1") (pintype "passive"))
    )
    (net (code "93") (name "Net-(U1-MICNR)") (class "Default")
      (node (ref "C8") (pin "1") (pinfunction "1_1") (pintype "passive"))
      (node (ref "U1") (pin "19") (pinfunction "MICNR_19") (pintype "passive"))
    )
    (net (code "94") (name "Net-(U1-VCM)") (class "Default")
      (node (ref "C3") (pin "1") (pinfunction "1_1") (pintype "passive"))
      (node (ref "U1") (pin "23") (pinfunction "VCM_23") (pintype "passive"))
    )
    (net (code "95") (name "Net-(U1-VIN5V)") (class "Default")
      (node (ref "C2") (pin "1") (pinfunction "1_1") (pintype "passive"))
      (node (ref "R3") (pin "2") (pinfunction "2_2") (pintype "passive"))
      (node (ref "U1") (pin "2") (pinfunction "VIN5V_2") (pintype "passive"))
    )
    (net (code "96") (name "Net-(U15-IN)") (class "Default")
      (node (ref "C34") (pin "2") (pinfunction "2_2") (pintype "passive"))
      (node (ref "R38") (pin "2") (pinfunction "2_2") (pintype "passive"))
      (node (ref "U15") (pin "3") (pinfunction "IN_3") (pintype "passive"))
    )
    (net (code "97") (name "Net-(U19-DAT1)") (class "Default")
      (node (ref "R22") (pin "2") (pinfunction "2_2") (pintype "passive"))
      (node (ref "U19") (pin "1") (pinfunction "DAT2_1") (pintype "passive"))
      (node (ref "U19") (pin "8") (pinfunction "DAT1_8") (pintype "passive"))
    )
    (net (code "98") (name "Net-(U25-+IN)") (class "Default")
      (node (ref "C46") (pin "1") (pinfunction "1_1") (pintype "passive"))
      (node (ref "U25") (pin "2") (pinfunction "BYPASS_2") (pintype "passive"))
      (node (ref "U25") (pin "3") (pinfunction "+IN_3") (pintype "passive"))
    )
    (net (code "99") (name "Net-(U25--IN)") (class "Default")
      (node (ref "R48") (pin "2") (pinfunction "2_2") (pintype "passive"))
      (node (ref "R49") (pin "2") (pinfunction "2_2") (pintype "passive"))
      (node (ref "U25") (pin "4") (pinfunction "-IN_4") (pintype "passive"))
    )
    (net (code "100") (name "TW_VCC") (class "Default")
      (node (ref "C47") (pin "1") (pinfunction "1_1") (pintype "passive"))
      (node (ref "R12") (pin "1") (pinfunction "1_1") (pintype "passive"))
      (node (ref "R3") (pin "1") (pinfunction "1_1") (pintype "passive"))
      (node (ref "R6") (pin "1") (pinfunction "1_1") (pintype "passive"))
      (node (ref "R7") (pin "1") (pinfunction "1_1") (pintype "passive"))
      (node (ref "U25") (pin "6") (pinfunction "VDD_6") (pintype "passive"))
      (node (ref "U6") (pin "1") (pinfunction "C_1") (pintype "passive"))
    )
    (net (code "101") (name "VCC_3V3") (class "Default")
      (node (ref "C17") (pin "2") (pinfunction "2_2") (pintype "passive"))
      (node (ref "C18") (pin "2") (pinfunction "2_2") (pintype "passive"))
      (node (ref "C35") (pin "1") (pinfunction "1_1") (pintype "passive"))
      (node (ref "R20") (pin "1") (pinfunction "1_1") (pintype "passive"))
      (node (ref "R21") (pin "1") (pinfunction "1_1") (pintype "passive"))
      (node (ref "R22") (pin "1") (pinfunction "1_1") (pintype "passive"))
      (node (ref "R29") (pin "1") (pinfunction "1_1") (pintype "passive"))
      (node (ref "R41") (pin "1") (pinfunction "1_1") (pintype "passive"))
      (node (ref "R42") (pin "2") (pinfunction "2_2") (pintype "passive"))
      (node (ref "R45") (pin "1") (pinfunction "1_1") (pintype "passive"))
      (node (ref "U15") (pin "1") (pinfunction "OUT_1") (pintype "passive"))
      (node (ref "U19") (pin "4") (pinfunction "VDD_4") (pintype "passive"))
      (node (ref "U22") (pin "3") (pinfunction "3_3") (pintype "passive"))
    )
    (net (code "103") (name "unconnected-(U14-ADC-Pad9)") (class "Default")
      (node (ref "U14") (pin "9") (pinfunction "ADC_9") (pintype "passive"))
    )
    (net (code "104") (name "unconnected-(U14-ANT_MAIN-Pad35)") (class "Default")
      (node (ref "U14") (pin "35") (pinfunction "ANT_MAIN_35") (pintype "passive"))
    )
    (net (code "105") (name "unconnected-(U14-BOOT_MODE-Pad82)") (class "Default")
      (node (ref "U14") (pin "82") (pinfunction "BOOT_MODE_82") (pintype "passive"))
    )
    (net (code "106") (name "unconnected-(U14-DBG_RXD-Pad38)") (class "Default")
      (node (ref "U14") (pin "38") (pinfunction "DBG_RXD_38") (pintype "passive"))
    )
    (net (code "107") (name "unconnected-(U14-DBG_TXD-Pad39)") (class "Default")
      (node (ref "U14") (pin "39") (pinfunction "DBG_TXD_39") (pintype "passive"))
    )
    (net (code "108") (name "unconnected-(U14-GND-Pad1)") (class "Default")
      (node (ref "U14") (pin "1") (pinfunction "GND_1") (pintype "passive"))
    )
    (net (code "109") (name "unconnected-(U14-GND-Pad10)") (class "Default")
      (node (ref "U14") (pin "10") (pinfunction "GND_10") (pintype "passive"))
    )
    (net (code "110") (name "unconnected-(U14-GND-Pad27)") (class "Default")
      (node (ref "U14") (pin "27") (pinfunction "GND_27") (pintype "passive"))
    )
    (net (code "111") (name "unconnected-(U14-GND-Pad34)") (class "Default")
      (node (ref "U14") (pin "34") (pinfunction "GND_34") (pintype "passive"))
    )
    (net (code "112") (name "unconnected-(U14-GND-Pad36)") (class "Default")
      (node (ref "U14") (pin "36") (pinfunction "GND_36") (pintype "passive"))
    )
    (net (code "113") (name "unconnected-(U14-GND-Pad37)") (class "Default")
      (node (ref "U14") (pin "37") (pinfunction "GND_37") (pintype "passive"))
    )
    (net (code "114") (name "unconnected-(U14-GND-Pad40)") (class "Default")
      (node (ref "U14") (pin "40") (pinfunction "GND_40") (pintype "passive"))
    )
    (net (code "115") (name "unconnected-(U14-GND-Pad41)") (class "Default")
      (node (ref "U14") (pin "41") (pinfunction "GND_41") (pintype "passive"))
    )
    (net (code "116") (name "unconnected-(U14-GND-Pad45)") (class "Default")
      (node (ref "U14") (pin "45") (pinfunction "GND_45") (pintype "passive"))
    )
    (net (code "117") (name "unconnected-(U14-GND-Pad46)") (class "Default")
      (node (ref "U14") (pin "46") (pinfunction "GND_46") (pintype "passive"))
    )
    (net (code "118") (name "unconnected-(U14-GND-Pad47)") (class "Default")
      (node (ref "U14") (pin "47") (pinfunction "GND_47") (pintype "passive"))
    )
    (net (code "119") (name "unconnected-(U14-GND-Pad48)") (class "Default")
      (node (ref "U14") (pin "48") (pinfunction "GND_48") (pintype "passive"))
    )
    (net (code "120") (name "unconnected-(U14-GND-Pad70)") (class "Default")
      (node (ref "U14") (pin "70") (pinfunction "GND_70") (pintype "passive"))
    )
    (net (code "121") (name "unconnected-(U14-GND-Pad71)") (class "Default")
      (node (ref "U14") (pin "71") (pinfunction "GND_71") (pintype "passive"))
    )
    (net (code "122") (name "unconnected-(U14-GND-Pad72)") (class "Default")
      (node (ref "U14") (pin "72") (pinfunction "GND_72") (pintype "passive"))
    )
    (net (code "123") (name "unconnected-(U14-GND-Pad73)") (class "Default")
      (node (ref "U14") (pin "73") (pinfunction "GND_73") (pintype "passive"))
    )
    (net (code "124") (name "unconnected-(U14-GND-Pad88)") (class "Default")
      (node (ref "U14") (pin "88") (pinfunction "GND_88") (pintype "passive"))
    )
    (net (code "125") (name "unconnected-(U14-GND-Pad89)") (class "Default")
      (node (ref "U14") (pin "89") (pinfunction "GND_89") (pintype "passive"))
    )
    (net (code "126") (name "unconnected-(U14-GND-Pad90)") (class "Default")
      (node (ref "U14") (pin "90") (pinfunction "GND_90") (pintype "passive"))
    )
    (net (code "127") (name "unconnected-(U14-GND-Pad91)") (class "Default")
      (node (ref "U14") (pin "91") (pinfunction "GND_91") (pintype "passive"))
    )
    (net (code "128") (name "unconnected-(U14-GND-Pad92)") (class "Default")
      (node (ref "U14") (pin "92") (pinfunction "GND_92") (pintype "passive"))
    )
    (net (code "129") (name "unconnected-(U14-GND-Pad93)") (class "Default")
      (node (ref "U14") (pin "93") (pinfunction "GND_93") (pintype "passive"))
    )
    (net (code "130") (name "unconnected-(U14-GND-Pad94)") (class "Default")
      (node (ref "U14") (pin "94") (pinfunction "GND_94") (pintype "passive"))
    )
    (net (code "131") (name "unconnected-(U14-GPIO0-Pad76)") (class "Default")
      (node (ref "U14") (pin "76") (pinfunction "GPIO0_76") (pintype "passive"))
    )
    (net (code "132") (name "unconnected-(U14-GPIO1-Pad77)") (class "Default")
      (node (ref "U14") (pin "77") (pinfunction "GPIO1_77") (pintype "passive"))
    )
    (net (code "133") (name "unconnected-(U14-GPIO2-Pad86)") (class "Default")
      (node (ref "U14") (pin "86") (pinfunction "GPIO2_86") (pintype "passive"))
    )
    (net (code "134") (name "unconnected-(U14-GPIO3-Pad87)") (class "Default")
      (node (ref "U14") (pin "87") (pinfunction "GPIO3_87") (pintype "passive"))
    )
    (net (code "135") (name "unconnected-(U14-MIC_N-Pad4)") (class "Default")
      (node (ref "U14") (pin "4") (pinfunction "MIC_N_4") (pintype "passive"))
    )
    (net (code "136") (name "unconnected-(U14-MIC_P-Pad3)") (class "Default")
      (node (ref "U14") (pin "3") (pinfunction "MIC_P_3") (pintype "passive"))
    )
    (net (code "137") (name "unconnected-(U14-NETLIGHT-Pad16)") (class "Default")
      (node (ref "U14") (pin "16") (pinfunction "NETLIGHT_16") (pintype "passive"))
    )
    (net (code "138") (name "unconnected-(U14-PWM0-Pad74)") (class "Default")
      (node (ref "U14") (pin "74") (pinfunction "PWM0_74") (pintype "passive"))
    )
    (net (code "139") (name "unconnected-(U14-PWM1-Pad75)") (class "Default")
      (node (ref "U14") (pin "75") (pinfunction "PWM1_75") (pintype "passive"))
    )
    (net (code "140") (name "unconnected-(U14-PWR_ON{slash}OFF-Pad7)") (class "Default")
      (node (ref "U14") (pin "7") (pinfunction "PWR_ON/OFF_7") (pintype "passive"))
    )
    (net (code "141") (name "unconnected-(U14-RESET-Pad15)") (class "Default")
      (node (ref "U14") (pin "15") (pinfunction "RESET_15") (pintype "passive"))
    )
    (net (code "142") (name "unconnected-(U14-RSV-Pad2)") (class "Default")
      (node (ref "U14") (pin "2") (pinfunction "RSV_2") (pintype "passive"))
    )
    (net (code "143") (name "unconnected-(U14-RSV-Pad8)") (class "Default")
      (node (ref "U14") (pin "8") (pinfunction "RSV_8") (pintype "passive"))
    )
    (net (code "144") (name "unconnected-(U14-RSV-Pad26)") (class "Default")
      (node (ref "U14") (pin "26") (pinfunction "RSV_26") (pintype "passive"))
    )
    (net (code "145") (name "unconnected-(U14-RSV-Pad30)") (class "Default")
      (node (ref "U14") (pin "30") (pinfunction "RSV_30") (pintype "passive"))
    )
    (net (code "146") (name "unconnected-(U14-RSV-Pad31)") (class "Default")
      (node (ref "U14") (pin "31") (pinfunction "RSV_31") (pintype "passive"))
    )
    (net (code "147") (name "unconnected-(U14-RSV-Pad32)") (class "Default")
      (node (ref "U14") (pin "32") (pinfunction "RSV_32") (pintype "passive"))
    )
    (net (code "148") (name "unconnected-(U14-RSV-Pad33)") (class "Default")
      (node (ref "U14") (pin "33") (pinfunction "RSV_33") (pintype "passive"))
    )
    (net (code "149") (name "unconnected-(U14-RSV-Pad44)") (class "Default")
      (node (ref "U14") (pin "44") (pinfunction "RSV_44") (pintype "passive"))
    )
    (net (code "150") (name "unconnected-(U14-RSV-Pad50)") (class "Default")
      (node (ref "U14") (pin "50") (pinfunction "RSV_50") (pintype "passive"))
    )
    (net (code "151") (name "unconnected-(U14-RSV-Pad51)") (class "Default")
      (node (ref "U14") (pin "51") (pinfunction "RSV_51") (pintype "passive"))
    )
    (net (code "152") (name "unconnected-(U14-RSV-Pad52)") (class "Default")
      (node (ref "U14") (pin "52") (pinfunction "RSV_52") (pintype "passive"))
    )
    (net (code "153") (name "unconnected-(U14-RSV-Pad53)") (class "Default")
      (node (ref "U14") (pin "53") (pinfunction "RSV_53") (pintype "passive"))
    )
    (net (code "154") (name "unconnected-(U14-RSV-Pad54)") (class "Default")
      (node (ref "U14") (pin "54") (pinfunction "RSV_54") (pintype "passive"))
    )
    (net (code "155") (name "unconnected-(U14-RSV-Pad55)") (class "Default")
      (node (ref "U14") (pin "55") (pinfunction "RSV_55") (pintype "passive"))
    )
    (net (code "156") (name "unconnected-(U14-RSV-Pad56)") (class "Default")
      (node (ref "U14") (pin "56") (pinfunction "RSV_56") (pintype "passive"))
    )
    (net (code "157") (name "unconnected-(U14-RSV-Pad57)") (class "Default")
      (node (ref "U14") (pin "57") (pinfunction "RSV_57") (pintype "passive"))
    )
    (net (code "158") (name "unconnected-(U14-RSV-Pad58)") (class "Default")
      (node (ref "U14") (pin "58") (pinfunction "RSV_58") (pintype "passive"))
    )
    (net (code "159") (name "unconnected-(U14-RSV-Pad66)") (class "Default")
      (node (ref "U14") (pin "66") (pinfunction "RSV_66") (pintype "passive"))
    )
    (net (code "160") (name "unconnected-(U14-RSV-Pad67)") (class "Default")
      (node (ref "U14") (pin "67") (pinfunction "RSV_67") (pintype "passive"))
    )
    (net (code "161") (name "unconnected-(U14-RSV-Pad68)") (class "Default")
      (node (ref "U14") (pin "68") (pinfunction "RSV_68") (pintype "passive"))
    )
    (net (code "162") (name "unconnected-(U14-RSV-Pad69)") (class "Default")
      (node (ref "U14") (pin "69") (pinfunction "RSV_69") (pintype "passive"))
    )
    (net (code "163") (name "unconnected-(U14-RSV-Pad78)") (class "Default")
      (node (ref "U14") (pin "78") (pinfunction "RSV_78") (pintype "passive"))
    )
    (net (code "164") (name "unconnected-(U14-RSV-Pad80)") (class "Default")
      (node (ref "U14") (pin "80") (pinfunction "RSV_80") (pintype "passive"))
    )
    (net (code "165") (name "unconnected-(U14-RSV-Pad81)") (class "Default")
      (node (ref "U14") (pin "81") (pinfunction "RSV_81") (pintype "passive"))
    )
    (net (code "166") (name "unconnected-(U14-RSV-Pad83)") (class "Default")
      (node (ref "U14") (pin "83") (pinfunction "RSV_83") (pintype "passive"))
    )
    (net (code "167") (name "unconnected-(U14-RSV-Pad84)") (class "Default")
      (node (ref "U14") (pin "84") (pinfunction "RSV_84") (pintype "passive"))
    )
    (net (code "168") (name "unconnected-(U14-RSV-Pad85)") (class "Default")
      (node (ref "U14") (pin "85") (pinfunction "RSV_85") (pintype "passive"))
    )
    (net (code "169") (name "unconnected-(U14-SIM0_CLK-Pad13)") (class "Default")
      (node (ref "U14") (pin "13") (pinfunction "SIM0_CLK_13") (pintype "passive"))
    )
    (net (code "170") (name "unconnected-(U14-SIM0_DATA-Pad11)") (class "Default")
      (node (ref "U14") (pin "11") (pinfunction "SIM0_DATA_11") (pintype "passive"))
    )
    (net (code "171") (name "unconnected-(U14-SIM0_DET-Pad79)") (class "Default")
      (node (ref "U14") (pin "79") (pinfunction "SIM0_DET_79") (pintype "passive"))
    )
    (net (code "172") (name "unconnected-(U14-SIM0_RST-Pad12)") (class "Default")
      (node (ref "U14") (pin "12") (pinfunction "SIM0_RST_12") (pintype "passive"))
    )
    (net (code "173") (name "unconnected-(U14-SIM0_VCC-Pad14)") (class "Default")
      (node (ref "U14") (pin "14") (pinfunction "SIM0_VCC_14") (pintype "passive"))
    )
    (net (code "174") (name "unconnected-(U14-SIM1_CLK-Pad62)") (class "Default")
      (node (ref "U14") (pin "62") (pinfunction "SIM1_CLK_62") (pintype "passive"))
    )
    (net (code "175") (name "unconnected-(U14-SIM1_DATA-Pad64)") (class "Default")
      (node (ref "U14") (pin "64") (pinfunction "SIM1_DATA_64") (pintype "passive"))
    )
    (net (code "176") (name "unconnected-(U14-SIM1_RST-Pad63)") (class "Default")
      (node (ref "U14") (pin "63") (pinfunction "SIM1_RST_63") (pintype "passive"))
    )
    (net (code "177") (name "unconnected-(U14-SIM1_VCC-Pad65)") (class "Default")
      (node (ref "U14") (pin "65") (pinfunction "SIM1_VCC_65") (pintype "passive"))
    )
    (net (code "178") (name "unconnected-(U14-SPK_N-Pad6)") (class "Default")
      (node (ref "U14") (pin "6") (pinfunction "SPK_N_6") (pintype "passive"))
    )
    (net (code "179") (name "unconnected-(U14-SPK_P-Pad5)") (class "Default")
      (node (ref "U14") (pin "5") (pinfunction "SPK_P_5") (pintype "passive"))
    )
    (net (code "180") (name "unconnected-(U14-STATE-Pad25)") (class "Default")
      (node (ref "U14") (pin "25") (pinfunction "STATE_25") (pintype "passive"))
    )
    (net (code "181") (name "unconnected-(U14-UART0_CTS-Pad22)") (class "Default")
      (node (ref "U14") (pin "22") (pinfunction "UART0_CTS_22") (pintype "passive"))
    )
    (net (code "182") (name "unconnected-(U14-UART0_DCD-Pad21)") (class "Default")
      (node (ref "U14") (pin "21") (pinfunction "UART0_DCD_21") (pintype "passive"))
    )
    (net (code "183") (name "unconnected-(U14-UART0_DTR-Pad19)") (class "Default")
      (node (ref "U14") (pin "19") (pinfunction "UART0_DTR_19") (pintype "passive"))
    )
    (net (code "184") (name "unconnected-(U14-UART0_RI-Pad20)") (class "Default")
      (node (ref "U14") (pin "20") (pinfunction "UART0_RI_20") (pintype "passive"))
    )
    (net (code "185") (name "unconnected-(U14-UART0_RTS-Pad23)") (class "Default")
      (node (ref "U14") (pin "23") (pinfunction "UART0_RTS_23") (pintype "passive"))
    )
    (net (code "186") (name "unconnected-(U14-UART0_RXD-Pad17)") (class "Default")
      (node (ref "U14") (pin "17") (pinfunction "UART0_RXD_17") (pintype "passive"))
    )
    (net (code "187") (name "unconnected-(U14-UART0_TXD-Pad18)") (class "Default")
      (node (ref "U14") (pin "18") (pinfunction "UART0_TXD_18") (pintype "passive"))
    )
    (net (code "188") (name "unconnected-(U14-UART1_RXD*-Pad28)") (class "Default")
      (node (ref "U14") (pin "28") (pinfunction "UART1_RXD*_28") (pintype "passive"))
    )
    (net (code "189") (name "unconnected-(U14-UART1_TXD*-Pad29)") (class "Default")
      (node (ref "U14") (pin "29") (pinfunction "UART1_TXD*_29") (pintype "passive"))
    )
    (net (code "190") (name "unconnected-(U14-USB_DM-Pad60)") (class "Default")
      (node (ref "U14") (pin "60") (pinfunction "USB_DM_60") (pintype "passive"))
    )
    (net (code "191") (name "unconnected-(U14-USB_DP-Pad59)") (class "Default")
      (node (ref "U14") (pin "59") (pinfunction "USB_DP_59") (pintype "passive"))
    )
    (net (code "192") (name "unconnected-(U14-USB_VBUS-Pad61)") (class "Default")
      (node (ref "U14") (pin "61") (pinfunction "USB_VBUS_61") (pintype "passive"))
    )
    (net (code "193") (name "unconnected-(U14-VBAT-Pad42)") (class "Default")
      (node (ref "U14") (pin "42") (pinfunction "VBAT_42") (pintype "passive"))
    )
    (net (code "194") (name "unconnected-(U14-VBAT-Pad43)") (class "Default")
      (node (ref "U14") (pin "43") (pinfunction "VBAT_43") (pintype "passive"))
    )
    (net (code "195") (name "unconnected-(U14-VDD_EXT-Pad24)") (class "Default")
      (node (ref "U14") (pin "24") (pinfunction "VDD_EXT_24") (pintype "passive"))
    )
    (net (code "196") (name "unconnected-(U14-WAKEUP_OUT-Pad49)") (class "Default")
      (node (ref "U14") (pin "49") (pinfunction "WAKEUP_OUT_49") (pintype "passive"))
    )
    (net (code "197") (name "unconnected-(U16-SBU1-PadA8)") (class "Default")
      (node (ref "U16") (pin "A8") (pinfunction "SBU1_A8") (pintype "passive+no_connect"))
    )
    (net (code "198") (name "unconnected-(U16-SBU2-PadB8)") (class "Default")
      (node (ref "U16") (pin "B8") (pinfunction "SBU2_B8") (pintype "passive+no_connect"))
    )
    (net (code "199") (name "unconnected-(U19-CD-Pad9)") (class "Default")
      (node (ref "U19") (pin "9") (pinfunction "CD_9") (pintype "passive"))
    )
    (net (code "200") (name "unconnected-(U23-N.C.-Pad5)") (class "Default")
      (node (ref "U23") (pin "5") (pinfunction "N.C._5") (pintype "passive+no_connect"))
    )
    (net (code "201") (name "unconnected-(U23-N.C.-Pad6)") (class "Default")
      (node (ref "U23") (pin "6") (pinfunction "N.C._6") (pintype "passive+no_connect"))
    )
    (net (code "202") (name "unconnected-(U23-N.C.-Pad12)") (class "Default")
      (node (ref "U23") (pin "12") (pinfunction "N.C._12") (pintype "passive+no_connect"))
    )
    (net (code "203") (name "unconnected-(U23-N.C.-Pad13)") (class "Default")
      (node (ref "U23") (pin "13") (pinfunction "N.C._13") (pintype "passive+no_connect"))
    )
  )
)
